# 255SB_to_Switch_SMD_double.net
KiCad netlist of a schematic drawn in EAGLE
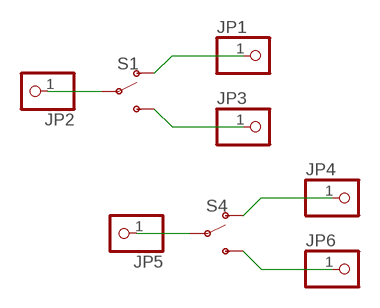
[diagram p0: schematic, sheet 1]

(export (version "E")
  (design (tool "Eeschema 10.0.6"))
  (components
    (comp (ref "JP1")
      (value "PINHD-1X01_2.54-SMD")
      (footprint "eagle-import:1X01SMD")
      (libsource (lib "eagle-import") (part "PINHD-1X01_2.54-SMD"))
    )
    (comp (ref "JP2")
      (value "PINHD-1X01_2.54-SMD")
      (footprint "eagle-import:1X01SMD")
      (libsource (lib "eagle-import") (part "PINHD-1X01_2.54-SMD"))
    )
    (comp (ref "JP3")
      (value "PINHD-1X01_2.54-SMD")
      (footprint "eagle-import:1X01SMD")
      (libsource (lib "eagle-import") (part "PINHD-1X01_2.54-SMD"))
    )
    (comp (ref "JP4")
      (value "PINHD-1X01_2.54-SMD")
      (footprint "eagle-import:1X01SMD")
      (libsource (lib "eagle-import") (part "PINHD-1X01_2.54-SMD"))
    )
    (comp (ref "JP5")
      (value "PINHD-1X01_2.54-SMD")
      (footprint "eagle-import:1X01SMD")
      (libsource (lib "eagle-import") (part "PINHD-1X01_2.54-SMD"))
    )
    (comp (ref "JP6")
      (value "PINHD-1X01_2.54-SMD")
      (footprint "eagle-import:1X01SMD")
      (libsource (lib "eagle-import") (part "PINHD-1X01_2.54-SMD"))
    )
    (comp (ref "S1")
      (value "SWITCH-SPDT-SMD-AYZ0202")
      (footprint "eagle-import:SWITCH_DPDT_SMD_AYZ0202")
      (libsource (lib "eagle-import") (part "SWITCH-SPDT-SMD-AYZ0202"))
    )
    (comp (ref "S4")
      (value "SWITCH-SPDT-SMD-AYZ0202")
      (footprint "eagle-import:SWITCH_DPDT_SMD_AYZ0202")
      (libsource (lib "eagle-import") (part "SWITCH-SPDT-SMD-AYZ0202"))
    )
  )
  (nets
    (net (code "1") (name "Net-(S1-O)") (class "Default")
      (node (ref "JP1") (pin "1") (pinfunction "1_1") (pintype "passive"))
      (node (ref "S1") (pin "1") (pinfunction "O_1") (pintype "passive"))
    )
    (net (code "2") (name "Net-(S1-P)") (class "Default")
      (node (ref "JP2") (pin "1") (pinfunction "1_1") (pintype "passive"))
      (node (ref "S1") (pin "2") (pinfunction "P_2") (pintype "passive"))
    )
    (net (code "3") (name "Net-(S1-S)") (class "Default")
      (node (ref "JP3") (pin "1") (pinfunction "1_1") (pintype "passive"))
      (node (ref "S1") (pin "3") (pinfunction "S_3") (pintype "passive"))
    )
    (net (code "4") (name "Net-(S4-O)") (class "Default")
      (node (ref "JP4") (pin "1") (pinfunction "1_1") (pintype "passive"))
      (node (ref "S4") (pin "1") (pinfunction "O_1") (pintype "passive"))
    )
    (net (code "5") (name "Net-(S4-P)") (class "Default")
      (node (ref "JP5") (pin "1") (pinfunction "1_1") (pintype "passive"))
      (node (ref "S4") (pin "2") (pinfunction "P_2") (pintype "passive"))
    )
    (net (code "6") (name "Net-(S4-S)") (class "Default")
      (node (ref "JP6") (pin "1") (pinfunction "1_1") (pintype "passive"))
      (node (ref "S4") (pin "3") (pinfunction "S_3") (pintype "passive"))
    )
  )
)
